# Communication.net
KiCad netlist of a schematic drawn in Altium Designer
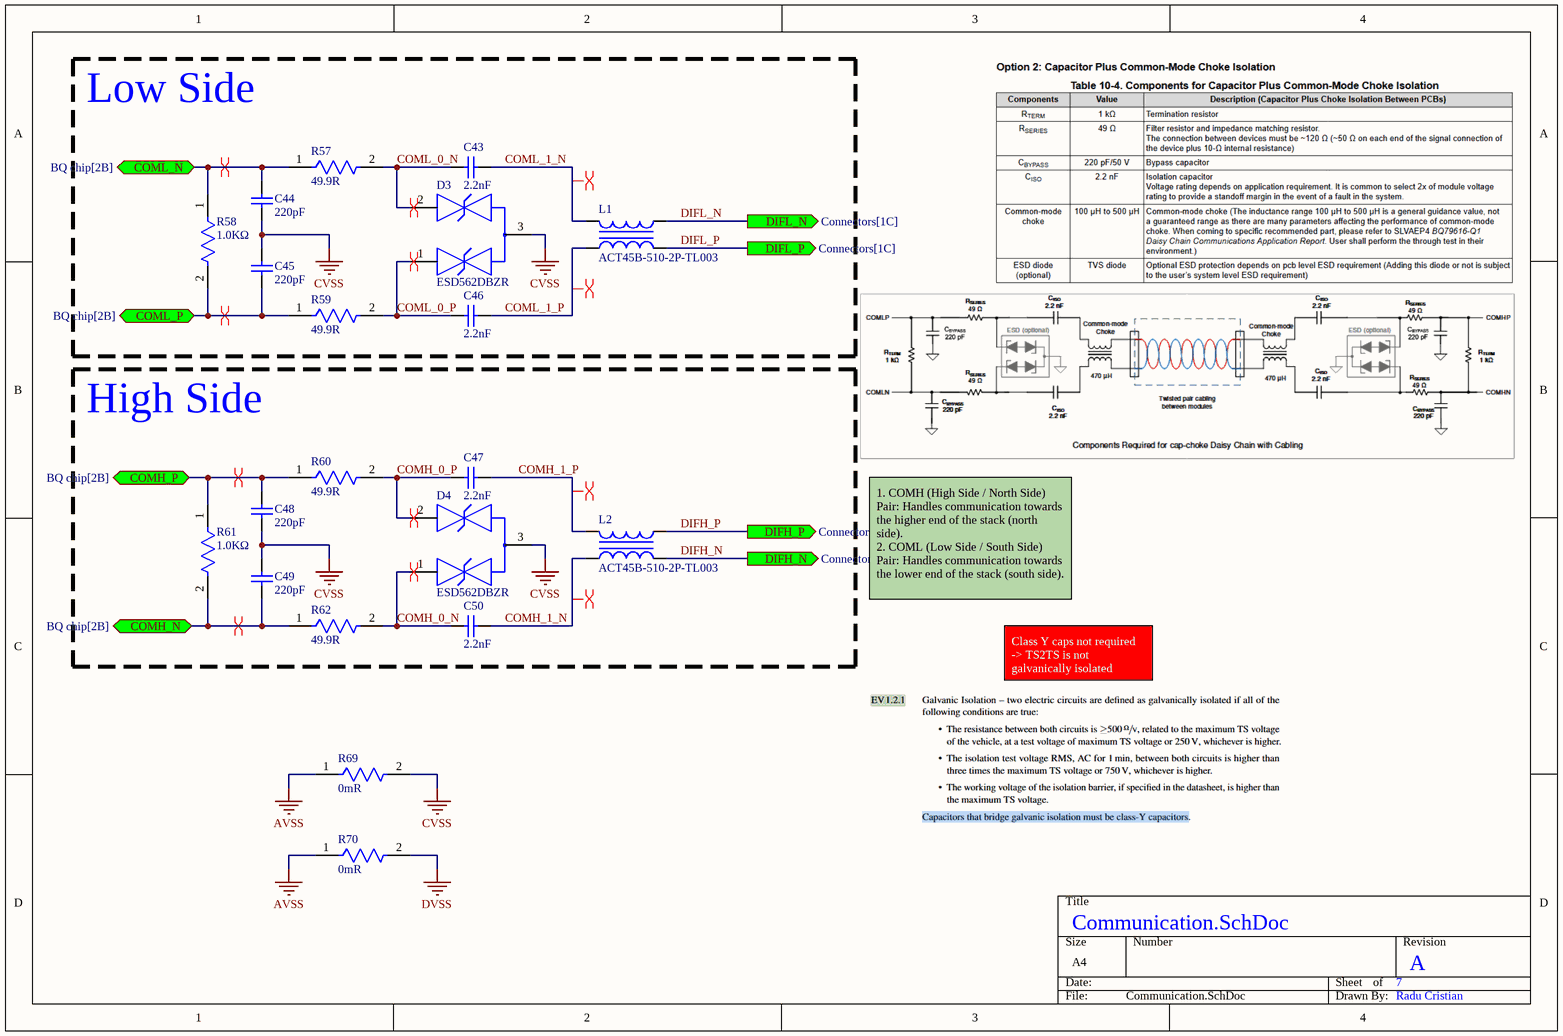
[diagram p0: Communication.SchDoc]

(export (version "E")
  (design (tool "Eeschema 10.0.6"))
  (components
    (comp (ref "C43")
      (value "VJ0603Y222JXBAC")
      (footprint "CAPC1608X92X38ML15T08")
      (fields (field (name "MANUFACTURER") "Vitramon") (field (name "PARAMETER 1") "2.2nF"))
      (libsource (lib "Altium Content Vault") (part "CAP"))
    )
    (comp (ref "C44")
      (value "220pF")
      (footprint "CAPC0603(1608)100_N")
      (description "CAP 220pF 100V ±10% 0603 (1608 Metric) Thickness 1mm SMD")
      (fields (field (name "TOLERANCE") "Â±10%") (field (name "Comment") "CAP 220pF 100V 0603(1608)"))
      (libsource (lib "Altium Content Vault") (part "CAP"))
    )
    (comp (ref "C45")
      (value "220pF")
      (footprint "CAPC0603(1608)100_N")
      (description "CAP 220pF 100V ±10% 0603 (1608 Metric) Thickness 1mm SMD")
      (fields (field (name "TOLERANCE") "Â±10%") (field (name "Comment") "CAP 220pF 100V 0603(1608)"))
      (libsource (lib "Altium Content Vault") (part "CAP"))
    )
    (comp (ref "C46")
      (value "VJ0603Y222JXBAC")
      (footprint "CAPC1608X92X38ML15T08")
      (fields (field (name "MANUFACTURER") "Vitramon") (field (name "PARAMETER 1") "2.2nF"))
      (libsource (lib "Altium Content Vault") (part "CAP"))
    )
    (comp (ref "C47")
      (value "VJ0603Y222JXBAC")
      (footprint "CAPC1608X92X38ML15T08")
      (fields (field (name "MANUFACTURER") "Vitramon") (field (name "PARAMETER 1") "2.2nF"))
      (libsource (lib "Altium Content Vault") (part "CAP"))
    )
    (comp (ref "C48")
      (value "220pF")
      (footprint "CAPC0603(1608)100_N")
      (description "CAP 220pF 100V ±10% 0603 (1608 Metric) Thickness 1mm SMD")
      (fields (field (name "TOLERANCE") "Â±10%") (field (name "Comment") "CAP 220pF 100V 0603(1608)"))
      (libsource (lib "Altium Content Vault") (part "CAP"))
    )
    (comp (ref "C49")
      (value "220pF")
      (footprint "CAPC0603(1608)100_N")
      (description "CAP 220pF 100V ±10% 0603 (1608 Metric) Thickness 1mm SMD")
      (fields (field (name "TOLERANCE") "Â±10%") (field (name "Comment") "CAP 220pF 100V 0603(1608)"))
      (libsource (lib "Altium Content Vault") (part "CAP"))
    )
    (comp (ref "C50")
      (value "VJ0603Y222JXBAC")
      (footprint "CAPC1608X92X38ML15T08")
      (fields (field (name "MANUFACTURER") "Vitramon") (field (name "PARAMETER 1") "2.2nF"))
      (libsource (lib "Altium Content Vault") (part "CAP"))
    )
    (comp (ref "D3")
      (value "ESD562DBZR")
      (footprint "FP-DBZ0003A-MFG")
      (description "ESD562DBZR Two-channel bidirectional 12V ESD protection diode 3-SOT-23 -40 to 125")
      (libsource (lib "Altium Content Vault") (part "6a230d497ab896455a1178b8499821c"))
    )
    (comp (ref "D4")
      (value "ESD562DBZR")
      (footprint "FP-DBZ0003A-MFG")
      (description "ESD562DBZR Two-channel bidirectional 12V ESD protection diode 3-SOT-23 -40 to 125")
      (libsource (lib "Altium Content Vault") (part "6a230d497ab896455a1178b8499821c"))
    )
    (comp (ref "L1")
      (value "ACT45B-510-2P-TL003")
      (footprint "TDK-ACT45B-510-2P-TL003-4_V")
      (fields (field (name "MANUFACTURER") "TDK"))
      (libsource (lib "Altium Content Vault") (part "TDK-ACXXXXX-XXX-2P-T000-4"))
    )
    (comp (ref "L2")
      (value "ACT45B-510-2P-TL003")
      (footprint "TDK-ACT45B-510-2P-TL003-4_V")
      (fields (field (name "MANUFACTURER") "TDK"))
      (libsource (lib "Altium Content Vault") (part "TDK-ACXXXXX-XXX-2P-T000-4"))
    )
    (comp (ref "R57")
      (value "CRCW060349R9FKECHP")
      (footprint "FP-CRCW0603-HPe3-MFG")
      (description "RES Thick Film, 49.9Ω, 1%, 0.33W, 100ppm/°C, 0603")
      (fields (field (name "TOLERANCE") "1%") (field (name "RESISTANCE") "49.9R"))
      (libsource (lib "Altium Content Vault") (part "1029c3af85768c4190bb7ad29bc67b5"))
    )
    (comp (ref "R58")
      (value "CPF0603F1K0C1")
      (footprint "FP-CPF0603-MFG")
      (description "RES SMD 1.0KΩ 1% 1/16W 0603")
      (fields
        (field (name "OCTOPART") "https://octopart.com/cpf0603f1k0c1-te+connectivity-42013134")
        (field (name "TOLERANCE") "1%")
        (field (name "RESISTANCE") "1.0KΩ")
      )
      (libsource (lib "Altium Content Vault") (part "1029c3af85768c4190bb7ad29bc67b5"))
    )
    (comp (ref "R59")
      (value "CRCW060349R9FKECHP")
      (footprint "FP-CRCW0603-HPe3-MFG")
      (description "RES Thick Film, 49.9Ω, 1%, 0.33W, 100ppm/°C, 0603")
      (fields (field (name "TOLERANCE") "1%") (field (name "RESISTANCE") "49.9R"))
      (libsource (lib "Altium Content Vault") (part "1029c3af85768c4190bb7ad29bc67b5"))
    )
    (comp (ref "R60")
      (value "CRCW060349R9FKECHP")
      (footprint "FP-CRCW0603-HPe3-MFG")
      (description "RES Thick Film, 49.9Ω, 1%, 0.33W, 100ppm/°C, 0603")
      (fields (field (name "TOLERANCE") "1%") (field (name "RESISTANCE") "49.9R"))
      (libsource (lib "Altium Content Vault") (part "1029c3af85768c4190bb7ad29bc67b5"))
    )
    (comp (ref "R61")
      (value "CPF0603F1K0C1")
      (footprint "FP-CPF0603-MFG")
      (description "RES SMD 1.0KΩ 1% 1/16W 0603")
      (fields
        (field (name "OCTOPART") "https://octopart.com/cpf0603f1k0c1-te+connectivity-42013134")
        (field (name "TOLERANCE") "1%")
        (field (name "RESISTANCE") "1.0KΩ")
      )
      (libsource (lib "Altium Content Vault") (part "1029c3af85768c4190bb7ad29bc67b5"))
    )
    (comp (ref "R62")
      (value "CRCW060349R9FKECHP")
      (footprint "FP-CRCW0603-HPe3-MFG")
      (description "RES Thick Film, 49.9Ω, 1%, 0.33W, 100ppm/°C, 0603")
      (fields (field (name "TOLERANCE") "1%") (field (name "RESISTANCE") "49.9R"))
      (libsource (lib "Altium Content Vault") (part "1029c3af85768c4190bb7ad29bc67b5"))
    )
    (comp (ref "R69")
      (value "MCT06030Z0000ZPW00")
      (footprint "FP-MCT0603-MFG")
      (description "RES SMD 100 OHM 1% 1/8W 0603")
      (fields (field (name "RESISTANCE") "0mR"))
      (libsource (lib "Altium Content Vault") (part "1029c3af85768c4190bb7ad29bc67b5"))
    )
    (comp (ref "R70")
      (value "MCT06030Z0000ZPW00")
      (footprint "FP-MCT0603-MFG")
      (description "RES SMD 100 OHM 1% 1/8W 0603")
      (fields (field (name "RESISTANCE") "0mR"))
      (libsource (lib "Altium Content Vault") (part "1029c3af85768c4190bb7ad29bc67b5"))
    )
  )
  (nets
    (net (code "1") (name "/COMH_0_N") (class "Default")
      (node (ref "C50") (pin "2") (pinfunction "2_2") (pintype "passive"))
      (node (ref "D4") (pin "1") (pinfunction "1_IO_1") (pintype "passive"))
      (node (ref "R62") (pin "2") (pinfunction "2_2") (pintype "passive"))
    )
    (net (code "2") (name "/COMH_0_P") (class "Default")
      (node (ref "C47") (pin "2") (pinfunction "2_2") (pintype "passive"))
      (node (ref "D4") (pin "2") (pinfunction "2_IO_2") (pintype "passive"))
      (node (ref "R60") (pin "2") (pinfunction "2_2") (pintype "passive"))
    )
    (net (code "3") (name "/COMH_1_N") (class "Default")
      (node (ref "C50") (pin "1") (pinfunction "1_1") (pintype "passive"))
      (node (ref "L2") (pin "2") (pinfunction "2_2") (pintype "passive"))
    )
    (net (code "4") (name "/COMH_1_P") (class "Default")
      (node (ref "C47") (pin "1") (pinfunction "1_1") (pintype "passive"))
      (node (ref "L2") (pin "1") (pinfunction "1_1") (pintype "passive"))
    )
    (net (code "5") (name "/COMH_N") (class "Default")
      (node (ref "C49") (pin "2") (pinfunction "2_2") (pintype "passive"))
      (node (ref "R61") (pin "2") (pinfunction "2_2") (pintype "passive"))
      (node (ref "R62") (pin "1") (pinfunction "1_1") (pintype "passive"))
    )
    (net (code "6") (name "/COMH_P") (class "Default")
      (node (ref "C48") (pin "1") (pinfunction "1_1") (pintype "passive"))
      (node (ref "R60") (pin "1") (pinfunction "1_1") (pintype "passive"))
      (node (ref "R61") (pin "1") (pinfunction "1_1") (pintype "passive"))
    )
    (net (code "7") (name "/COML_0_N") (class "Default")
      (node (ref "C43") (pin "2") (pinfunction "2_2") (pintype "passive"))
      (node (ref "D3") (pin "2") (pinfunction "2_IO_2") (pintype "passive"))
      (node (ref "R57") (pin "2") (pinfunction "2_2") (pintype "passive"))
    )
    (net (code "8") (name "/COML_0_P") (class "Default")
      (node (ref "C46") (pin "2") (pinfunction "2_2") (pintype "passive"))
      (node (ref "D3") (pin "1") (pinfunction "1_IO_1") (pintype "passive"))
      (node (ref "R59") (pin "2") (pinfunction "2_2") (pintype "passive"))
    )
    (net (code "9") (name "/COML_1_N") (class "Default")
      (node (ref "C43") (pin "1") (pinfunction "1_1") (pintype "passive"))
      (node (ref "L1") (pin "1") (pinfunction "1_1") (pintype "passive"))
    )
    (net (code "10") (name "/COML_1_P") (class "Default")
      (node (ref "C46") (pin "1") (pinfunction "1_1") (pintype "passive"))
      (node (ref "L1") (pin "2") (pinfunction "2_2") (pintype "passive"))
    )
    (net (code "11") (name "/COML_N") (class "Default")
      (node (ref "C44") (pin "1") (pinfunction "1_1") (pintype "passive"))
      (node (ref "R57") (pin "1") (pinfunction "1_1") (pintype "passive"))
      (node (ref "R58") (pin "1") (pinfunction "1_1") (pintype "passive"))
    )
    (net (code "12") (name "/COML_P") (class "Default")
      (node (ref "C45") (pin "2") (pinfunction "2_2") (pintype "passive"))
      (node (ref "R58") (pin "2") (pinfunction "2_2") (pintype "passive"))
      (node (ref "R59") (pin "1") (pinfunction "1_1") (pintype "passive"))
    )
    (net (code "13") (name "/DIFH_N") (class "Default")
      (node (ref "L2") (pin "3") (pinfunction "3_3") (pintype "passive"))
    )
    (net (code "14") (name "/DIFH_P") (class "Default")
      (node (ref "L2") (pin "4") (pinfunction "4_4") (pintype "passive"))
    )
    (net (code "15") (name "/DIFL_N") (class "Default")
      (node (ref "L1") (pin "4") (pinfunction "4_4") (pintype "passive"))
    )
    (net (code "16") (name "/DIFL_P") (class "Default")
      (node (ref "L1") (pin "3") (pinfunction "3_3") (pintype "passive"))
    )
    (net (code "17") (name "AVSS") (class "Default")
      (node (ref "R69") (pin "1") (pinfunction "1_1") (pintype "passive"))
      (node (ref "R70") (pin "1") (pinfunction "1_1") (pintype "passive"))
    )
    (net (code "18") (name "CVSS") (class "Default")
      (node (ref "C44") (pin "2") (pinfunction "2_2") (pintype "passive"))
      (node (ref "C45") (pin "1") (pinfunction "1_1") (pintype "passive"))
      (node (ref "C48") (pin "2") (pinfunction "2_2") (pintype "passive"))
      (node (ref "C49") (pin "1") (pinfunction "1_1") (pintype "passive"))
      (node (ref "D3") (pin "3") (pinfunction "GND_3") (pintype "power_in"))
      (node (ref "D4") (pin "3") (pinfunction "GND_3") (pintype "power_in"))
      (node (ref "R69") (pin "2") (pinfunction "2_2") (pintype "passive"))
    )
    (net (code "19") (name "DVSS") (class "Default")
      (node (ref "R70") (pin "2") (pinfunction "2_2") (pintype "passive"))
    )
  )
)
